# ATSAMD11C14A.net
KiCad netlist of a schematic drawn in EAGLE
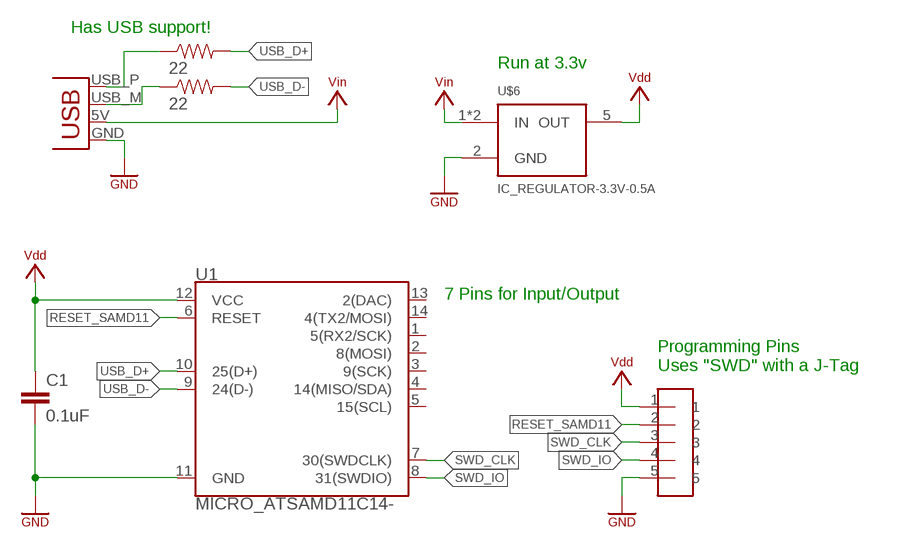
[diagram p0: schematic, sheet 1]

(export (version "E")
  (design (tool "Eeschema 10.0.6"))
  (components
    (comp (ref "C1")
      (value "0.1uF")
      (footprint "eagle-import:0805")
      (libsource (lib "eagle-import") (part "COMPONENT_CAP-0805"))
    )
    (comp (ref "R1")
      (value "22")
      (footprint "eagle-import:0805")
      (libsource (lib "eagle-import") (part "COMPONENT_RESISTOR-0805"))
    )
    (comp (ref "R2")
      (value "22")
      (footprint "eagle-import:0805")
      (libsource (lib "eagle-import") (part "COMPONENT_RESISTOR-0805"))
    )
    (comp (ref "U$3")
      (value "HEADER-5-TESTPOINT")
      (footprint "eagle-import:TESTPOINT-5")
      (libsource (lib "eagle-import") (part "HEADER-5-TESTPOINT"))
    )
    (comp (ref "U$4")
      (value "CONN_USB_PCB")
      (footprint "eagle-import:USB-PCB")
      (libsource (lib "eagle-import") (part "CONN_USB_PCB"))
    )
    (comp (ref "U$6")
      (value "IC_REGULATOR-3.3V-0.5A")
      (footprint "eagle-import:SOT23-5")
      (libsource (lib "eagle-import") (part "IC_REGULATOR-3.3V-0.5A"))
    )
    (comp (ref "U1")
      (value "MICRO_ATSAMD11C14-")
      (footprint "eagle-import:SOIC14")
      (libsource (lib "eagle-import") (part "MICRO_ATSAMD11C14-"))
    )
  )
  (nets
    (net (code "1") (name "Net-(U$4-D+)") (class "Default")
      (node (ref "R1") (pin "1") (pinfunction "1_1") (pintype "passive"))
      (node (ref "U$4") (pin "USB_P") (pinfunction "D+_USB_P") (pintype "bidirectional"))
    )
    (net (code "2") (name "Net-(U$4-D-)") (class "Default")
      (node (ref "R2") (pin "1") (pinfunction "1_1") (pintype "passive"))
      (node (ref "U$4") (pin "USB_M") (pinfunction "D-_USB_M") (pintype "bidirectional"))
    )
    (net (code "3") (name "RESET_SAMD11") (class "Default")
      (node (ref "U$3") (pin "2") (pinfunction "2_2") (pintype "bidirectional"))
      (node (ref "U1") (pin "6") (pinfunction "RESET_6") (pintype "bidirectional"))
    )
    (net (code "4") (name "SWD_CLK") (class "Default")
      (node (ref "U$3") (pin "3") (pinfunction "3_3") (pintype "bidirectional"))
      (node (ref "U1") (pin "7") (pinfunction "30(SWDCLK)_7") (pintype "bidirectional"))
    )
    (net (code "5") (name "SWD_IO") (class "Default")
      (node (ref "U$3") (pin "4") (pinfunction "4_4") (pintype "bidirectional"))
      (node (ref "U1") (pin "8") (pinfunction "31(SWDIO)_8") (pintype "bidirectional"))
    )
    (net (code "6") (name "SYMBOL_GND") (class "Default")
      (node (ref "C1") (pin "2") (pinfunction "2_2") (pintype "passive"))
      (node (ref "U$3") (pin "5") (pinfunction "5_5") (pintype "bidirectional"))
      (node (ref "U$4") (pin "GND") (pinfunction "GND_GND") (pintype "bidirectional"))
      (node (ref "U$6") (pin "2") (pinfunction "GND_2") (pintype "bidirectional"))
      (node (ref "U1") (pin "11") (pinfunction "GND_11") (pintype "bidirectional"))
    )
    (net (code "7") (name "SYMBOL_VDD") (class "Default")
      (node (ref "C1") (pin "1") (pinfunction "1_1") (pintype "passive"))
      (node (ref "U$3") (pin "1") (pinfunction "1_1") (pintype "bidirectional"))
      (node (ref "U$6") (pin "5") (pinfunction "OUT_5") (pintype "bidirectional"))
      (node (ref "U1") (pin "12") (pinfunction "VCC_12") (pintype "bidirectional"))
    )
    (net (code "8") (name "SYMBOL_VIN") (class "Default")
      (node (ref "U$4") (pin "5V") (pinfunction "VBUS_5V") (pintype "bidirectional"))
      (node (ref "U$6") (pin "1") (pinfunction "IN_1") (pintype "bidirectional"))
      (node (ref "U$6") (pin "3") (pinfunction "IN_3") (pintype "bidirectional"))
    )
    (net (code "9") (name "USB_D+") (class "Default")
      (node (ref "R1") (pin "2") (pinfunction "2_2") (pintype "passive"))
      (node (ref "U1") (pin "10") (pinfunction "25(D+)_10") (pintype "bidirectional"))
    )
    (net (code "10") (name "USB_D-") (class "Default")
      (node (ref "R2") (pin "2") (pinfunction "2_2") (pintype "passive"))
      (node (ref "U1") (pin "9") (pinfunction "24(D-)_9") (pintype "bidirectional"))
    )
    (net (code "11") (name "unconnected-(U1-2(DAC)-Pad13)") (class "Default")
      (node (ref "U1") (pin "13") (pinfunction "2(DAC)_13") (pintype "bidirectional"))
    )
    (net (code "12") (name "unconnected-(U1-4(TX2{slash}MOSI)-Pad14)") (class "Default")
      (node (ref "U1") (pin "14") (pinfunction "4(TX2/MOSI)_14") (pintype "bidirectional"))
    )
    (net (code "13") (name "unconnected-(U1-5(RX2{slash}SCK)-Pad1)") (class "Default")
      (node (ref "U1") (pin "1") (pinfunction "5(RX2/SCK)_1") (pintype "bidirectional"))
    )
    (net (code "14") (name "unconnected-(U1-8(MOSI)-Pad2)") (class "Default")
      (node (ref "U1") (pin "2") (pinfunction "8(MOSI)_2") (pintype "bidirectional"))
    )
    (net (code "15") (name "unconnected-(U1-9(SCK)-Pad3)") (class "Default")
      (node (ref "U1") (pin "3") (pinfunction "9(SCK)_3") (pintype "bidirectional"))
    )
    (net (code "16") (name "unconnected-(U1-14(MISO{slash}SDA)-Pad4)") (class "Default")
      (node (ref "U1") (pin "4") (pinfunction "14(MISO/SDA)_4") (pintype "bidirectional"))
    )
    (net (code "17") (name "unconnected-(U1-15(SCL)-Pad5)") (class "Default")
      (node (ref "U1") (pin "5") (pinfunction "15(SCL)_5") (pintype "bidirectional"))
    )
  )
)
